# project_2_DDR.net
KiCad netlist of a schematic drawn in EAGLE
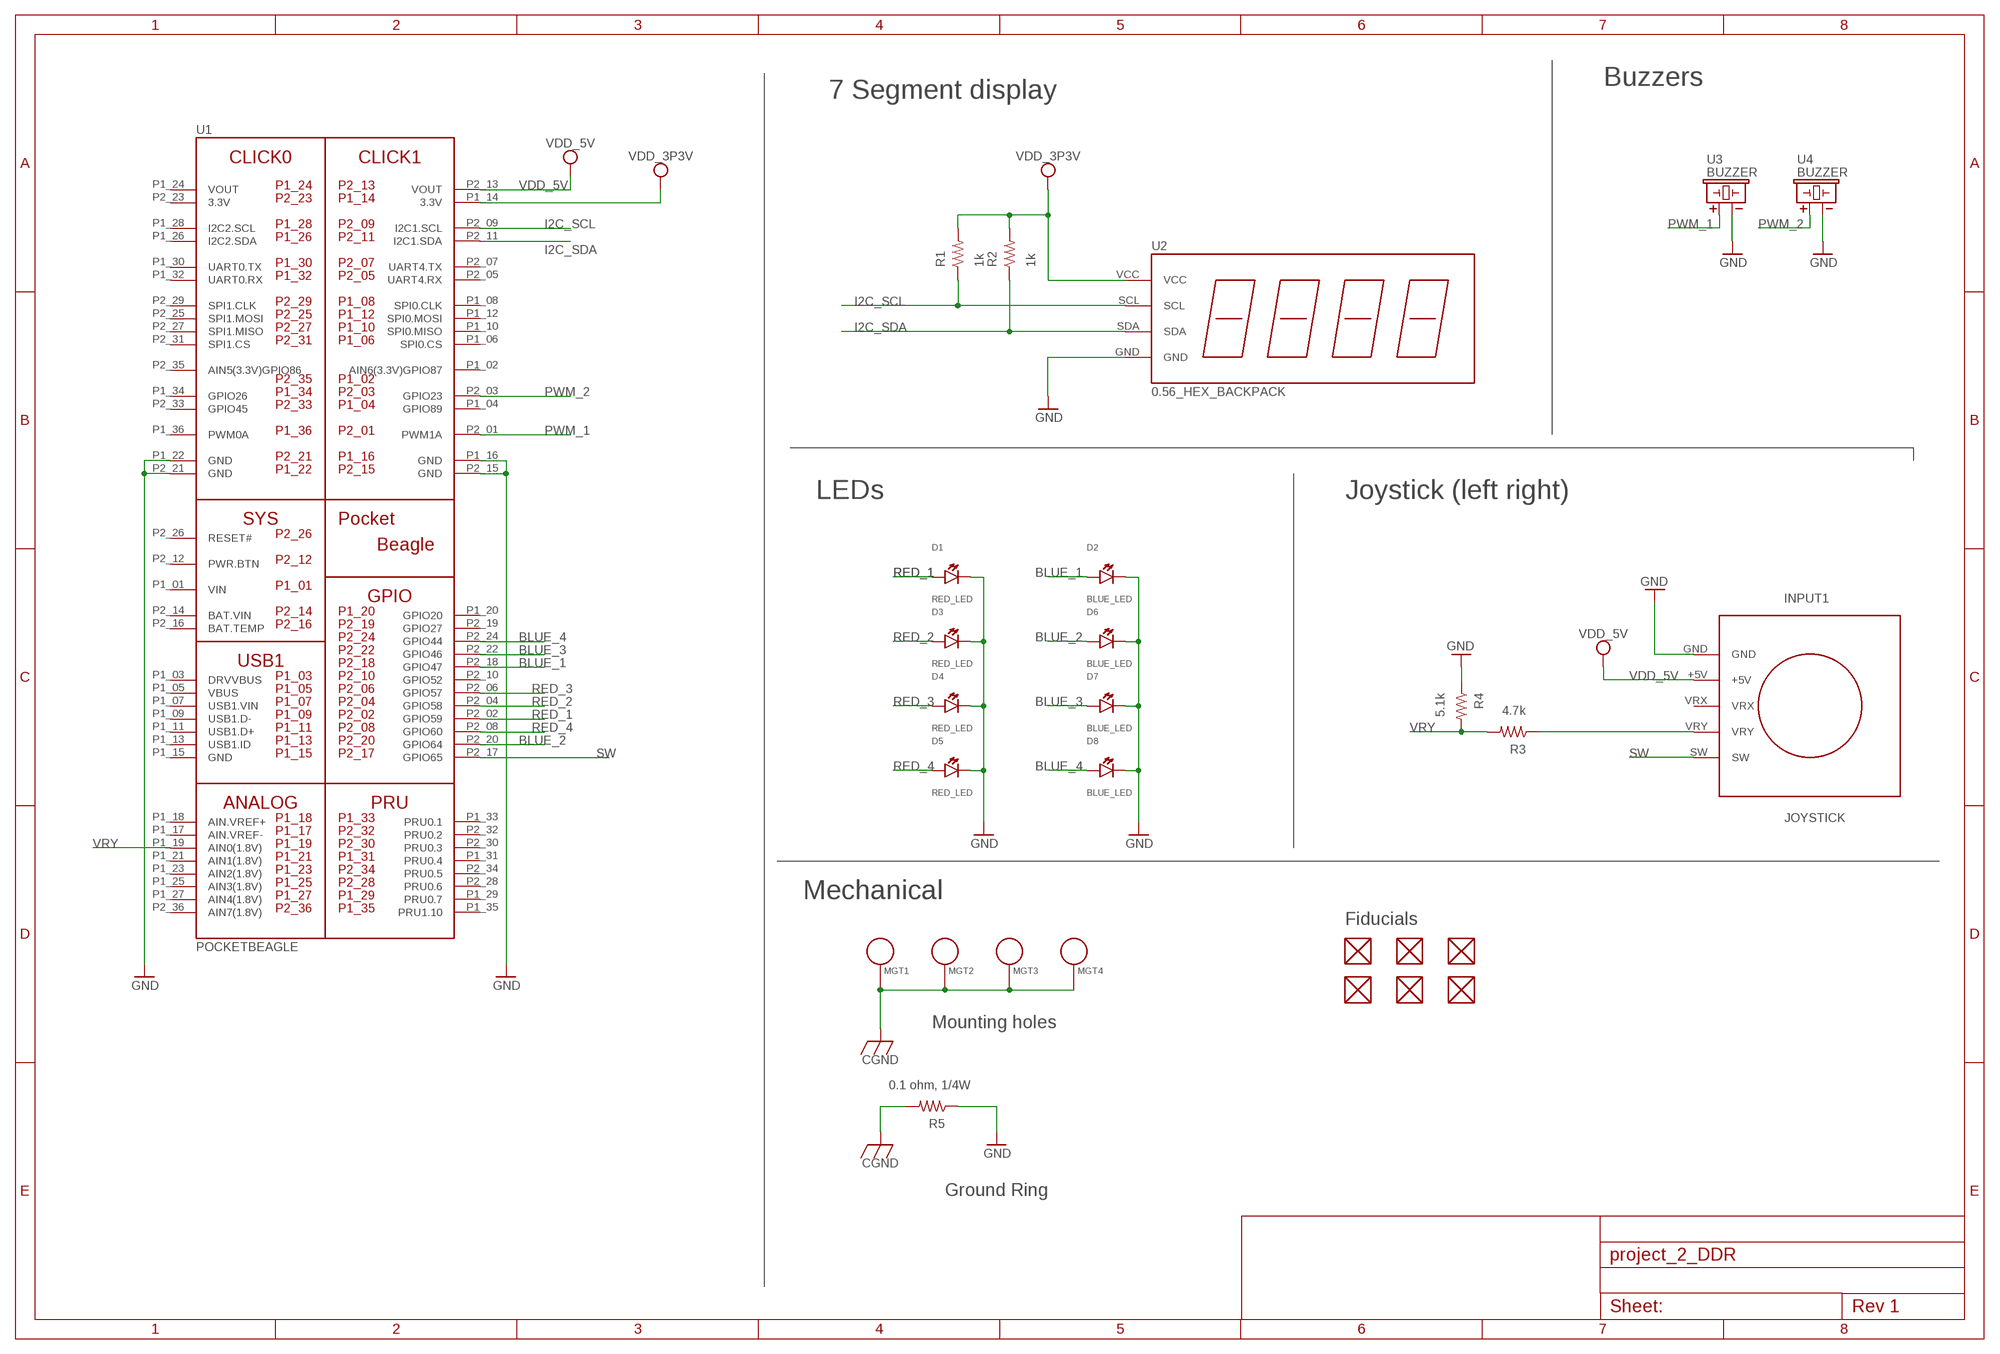
[diagram p0: schematic, sheet 1]

(export (version "E")
  (design (tool "Eeschema 10.0.6"))
  (components
    (comp (ref "D1")
      (value "RED_LED")
      (footprint "eagle-import:EIA-STD")
      (libsource (lib "eagle-import") (part "LED"))
    )
    (comp (ref "D2")
      (value "BLUE_LED")
      (footprint "eagle-import:EIA-STD")
      (libsource (lib "eagle-import") (part "LED"))
    )
    (comp (ref "D3")
      (value "RED_LED")
      (footprint "eagle-import:EIA-STD")
      (libsource (lib "eagle-import") (part "LED"))
    )
    (comp (ref "D4")
      (value "RED_LED")
      (footprint "eagle-import:EIA-STD")
      (libsource (lib "eagle-import") (part "LED"))
    )
    (comp (ref "D5")
      (value "RED_LED")
      (footprint "eagle-import:EIA-STD")
      (libsource (lib "eagle-import") (part "LED"))
    )
    (comp (ref "D6")
      (value "BLUE_LED")
      (footprint "eagle-import:EIA-STD")
      (libsource (lib "eagle-import") (part "LED"))
    )
    (comp (ref "D7")
      (value "BLUE_LED")
      (footprint "eagle-import:EIA-STD")
      (libsource (lib "eagle-import") (part "LED"))
    )
    (comp (ref "D8")
      (value "BLUE_LED")
      (footprint "eagle-import:EIA-STD")
      (libsource (lib "eagle-import") (part "LED"))
    )
    (comp (ref "FUD1")
      (value "FIDUCIAL")
      (footprint "eagle-import:FIDUCIAL_40MIL")
      (libsource (lib "eagle-import") (part "FIDUCIAL"))
    )
    (comp (ref "FUD2")
      (value "FIDUCIAL")
      (footprint "eagle-import:FIDUCIAL_40MIL")
      (libsource (lib "eagle-import") (part "FIDUCIAL"))
    )
    (comp (ref "FUD3")
      (value "FIDUCIAL")
      (footprint "eagle-import:FIDUCIAL_40MIL")
      (libsource (lib "eagle-import") (part "FIDUCIAL"))
    )
    (comp (ref "FUD4")
      (value "FIDUCIAL")
      (footprint "eagle-import:FIDUCIAL_40MIL")
      (libsource (lib "eagle-import") (part "FIDUCIAL"))
    )
    (comp (ref "FUD5")
      (value "FIDUCIAL")
      (footprint "eagle-import:FIDUCIAL_40MIL")
      (libsource (lib "eagle-import") (part "FIDUCIAL"))
    )
    (comp (ref "FUD6")
      (value "FIDUCIAL")
      (footprint "eagle-import:FIDUCIAL_40MIL")
      (libsource (lib "eagle-import") (part "FIDUCIAL"))
    )
    (comp (ref "INPUT1")
      (value "JOYSTICK")
      (footprint "eagle-import:JOYSTICK")
      (libsource (lib "eagle-import") (part "JOYSTICK"))
    )
    (comp (ref "MGT1")
      (value "MOUNTING_HOLE")
      (footprint "eagle-import:MOUNTING_HOLE")
      (libsource (lib "eagle-import") (part "MOUNTING_HOLE"))
    )
    (comp (ref "MGT2")
      (value "MOUNTING_HOLE")
      (footprint "eagle-import:MOUNTING_HOLE")
      (libsource (lib "eagle-import") (part "MOUNTING_HOLE"))
    )
    (comp (ref "MGT3")
      (value "MOUNTING_HOLE")
      (footprint "eagle-import:MOUNTING_HOLE")
      (libsource (lib "eagle-import") (part "MOUNTING_HOLE"))
    )
    (comp (ref "MGT4")
      (value "MOUNTING_HOLE")
      (footprint "eagle-import:MOUNTING_HOLE")
      (libsource (lib "eagle-import") (part "MOUNTING_HOLE"))
    )
    (comp (ref "R1")
      (value "1k")
      (footprint "eagle-import:R0603")
      (libsource (lib "eagle-import") (part "R_R0603"))
    )
    (comp (ref "R2")
      (value "1k")
      (footprint "eagle-import:R0603")
      (libsource (lib "eagle-import") (part "R_R0603"))
    )
    (comp (ref "R3")
      (value "4.7k")
      (footprint "eagle-import:R0603")
      (libsource (lib "eagle-import") (part "R_R0603"))
    )
    (comp (ref "R4")
      (value "5.1k")
      (footprint "eagle-import:R0603")
      (libsource (lib "eagle-import") (part "R_R0603"))
    )
    (comp (ref "R5")
      (value "0.1 ohm, 1/4W")
      (footprint "eagle-import:R0603")
      (libsource (lib "eagle-import") (part "R_R0603"))
    )
    (comp (ref "U1")
      (value "POCKETBEAGLE")
      (footprint "eagle-import:POCKETBEAGLE")
      (libsource (lib "eagle-import") (part "POCKETBEAGLE"))
    )
    (comp (ref "U2")
      (value "0.56_HEX_BACKPACK")
      (footprint "eagle-import:0.56_HEX_BACKPACK")
      (libsource (lib "eagle-import") (part "0.56_HEX_BACKPACK"))
    )
    (comp (ref "U3")
      (value "BUZZER")
      (footprint "eagle-import:BUZZER_6.5MM")
      (libsource (lib "eagle-import") (part "BUZZER"))
    )
    (comp (ref "U4")
      (value "BUZZER")
      (footprint "eagle-import:BUZZER_6.5MM")
      (libsource (lib "eagle-import") (part "BUZZER"))
    )
  )
  (nets
    (net (code "1") (name "/3.3V") (class "Default")
      (node (ref "U1") (pin "P2_23") (pinfunction "3.3V_P2_23") (pintype "power_in"))
    )
    (net (code "2") (name "/BAT.VIN") (class "Default")
      (node (ref "U1") (pin "P2_14") (pinfunction "BAT.VIN_P2_14") (pintype "power_in"))
    )
    (net (code "3") (name "/BLUE_1") (class "Default")
      (node (ref "D2") (pin "ANODE") (pinfunction "ANODE_ANODE") (pintype "bidirectional"))
      (node (ref "U1") (pin "P2_18") (pinfunction "GPIO47_P2_18") (pintype "bidirectional"))
    )
    (net (code "4") (name "/BLUE_2") (class "Default")
      (node (ref "D6") (pin "ANODE") (pinfunction "ANODE_ANODE") (pintype "bidirectional"))
      (node (ref "U1") (pin "P2_20") (pinfunction "GPIO64_P2_20") (pintype "bidirectional"))
    )
    (net (code "5") (name "/BLUE_3") (class "Default")
      (node (ref "D7") (pin "ANODE") (pinfunction "ANODE_ANODE") (pintype "bidirectional"))
      (node (ref "U1") (pin "P2_22") (pinfunction "GPIO46_P2_22") (pintype "bidirectional"))
    )
    (net (code "6") (name "/BLUE_4") (class "Default")
      (node (ref "D8") (pin "ANODE") (pinfunction "ANODE_ANODE") (pintype "bidirectional"))
      (node (ref "U1") (pin "P2_24") (pinfunction "GPIO44_P2_24") (pintype "bidirectional"))
    )
    (net (code "7") (name "/I2C_SCL") (class "Default")
      (node (ref "R1") (pin "1") (pinfunction "1_1") (pintype "passive"))
      (node (ref "U1") (pin "P2_09") (pinfunction "I2C1.SCL_P2_09") (pintype "bidirectional"))
      (node (ref "U2") (pin "SCL") (pinfunction "SCL_SCL") (pintype "bidirectional"))
    )
    (net (code "8") (name "/I2C_SDA") (class "Default")
      (node (ref "R2") (pin "1") (pinfunction "1_1") (pintype "passive"))
      (node (ref "U1") (pin "P2_11") (pinfunction "I2C1.SDA_P2_11") (pintype "bidirectional"))
      (node (ref "U2") (pin "SDA") (pinfunction "SDA_SDA") (pintype "bidirectional"))
    )
    (net (code "9") (name "/PWM_1") (class "Default")
      (node (ref "U1") (pin "P2_01") (pinfunction "PWM1A_P2_01") (pintype "bidirectional"))
      (node (ref "U3") (pin "+") (pinfunction "+_+") (pintype "passive"))
    )
    (net (code "10") (name "/PWM_2") (class "Default")
      (node (ref "U1") (pin "P2_03") (pinfunction "GPIO23_P2_03") (pintype "bidirectional"))
      (node (ref "U4") (pin "+") (pinfunction "+_+") (pintype "passive"))
    )
    (net (code "11") (name "/RED_1") (class "Default")
      (node (ref "D1") (pin "ANODE") (pinfunction "ANODE_ANODE") (pintype "bidirectional"))
      (node (ref "U1") (pin "P2_02") (pinfunction "GPIO59_P2_02") (pintype "bidirectional"))
    )
    (net (code "12") (name "/RED_2") (class "Default")
      (node (ref "D3") (pin "ANODE") (pinfunction "ANODE_ANODE") (pintype "bidirectional"))
      (node (ref "U1") (pin "P2_04") (pinfunction "GPIO58_P2_04") (pintype "bidirectional"))
    )
    (net (code "13") (name "/RED_3") (class "Default")
      (node (ref "D4") (pin "ANODE") (pinfunction "ANODE_ANODE") (pintype "bidirectional"))
      (node (ref "U1") (pin "P2_06") (pinfunction "GPIO57_P2_06") (pintype "bidirectional"))
    )
    (net (code "14") (name "/RED_4") (class "Default")
      (node (ref "D5") (pin "ANODE") (pinfunction "ANODE_ANODE") (pintype "bidirectional"))
      (node (ref "U1") (pin "P2_08") (pinfunction "GPIO60_P2_08") (pintype "bidirectional"))
    )
    (net (code "15") (name "/SW") (class "Default")
      (node (ref "INPUT1") (pin "SW") (pinfunction "SW_SW") (pintype "output"))
      (node (ref "U1") (pin "P2_17") (pinfunction "GPIO65_P2_17") (pintype "bidirectional"))
    )
    (net (code "16") (name "/VIN") (class "Default")
      (node (ref "U1") (pin "P1_01") (pinfunction "VIN_P1_01") (pintype "power_in"))
    )
    (net (code "17") (name "/VOUT") (class "Default")
      (node (ref "U1") (pin "P1_24") (pinfunction "VOUT_P1_24") (pintype "power_in"))
    )
    (net (code "18") (name "/VRY") (class "Default")
      (node (ref "R3") (pin "2") (pinfunction "2_2") (pintype "passive"))
      (node (ref "R4") (pin "2") (pinfunction "2_2") (pintype "passive"))
      (node (ref "U1") (pin "P1_19") (pinfunction "AIN0(1.8V)_P1_19") (pintype "input"))
    )
    (net (code "19") (name "CGND") (class "Default")
      (node (ref "MGT1") (pin "P$1") (pinfunction "P$1_P$1") (pintype "bidirectional"))
      (node (ref "MGT2") (pin "P$1") (pinfunction "P$1_P$1") (pintype "bidirectional"))
      (node (ref "MGT3") (pin "P$1") (pinfunction "P$1_P$1") (pintype "bidirectional"))
      (node (ref "MGT4") (pin "P$1") (pinfunction "P$1_P$1") (pintype "bidirectional"))
      (node (ref "R5") (pin "2") (pinfunction "2_2") (pintype "passive"))
    )
    (net (code "20") (name "GND") (class "Default")
      (node (ref "D1") (pin "CATHODE") (pinfunction "CATHODE_CATHODE") (pintype "bidirectional"))
      (node (ref "D2") (pin "CATHODE") (pinfunction "CATHODE_CATHODE") (pintype "bidirectional"))
      (node (ref "D3") (pin "CATHODE") (pinfunction "CATHODE_CATHODE") (pintype "bidirectional"))
      (node (ref "D4") (pin "CATHODE") (pinfunction "CATHODE_CATHODE") (pintype "bidirectional"))
      (node (ref "D5") (pin "CATHODE") (pinfunction "CATHODE_CATHODE") (pintype "bidirectional"))
      (node (ref "D6") (pin "CATHODE") (pinfunction "CATHODE_CATHODE") (pintype "bidirectional"))
      (node (ref "D7") (pin "CATHODE") (pinfunction "CATHODE_CATHODE") (pintype "bidirectional"))
      (node (ref "D8") (pin "CATHODE") (pinfunction "CATHODE_CATHODE") (pintype "bidirectional"))
      (node (ref "INPUT1") (pin "GND") (pinfunction "GND_GND") (pintype "bidirectional"))
      (node (ref "R4") (pin "1") (pinfunction "1_1") (pintype "passive"))
      (node (ref "R5") (pin "1") (pinfunction "1_1") (pintype "passive"))
      (node (ref "U1") (pin "P1_16") (pinfunction "GND_P1_16") (pintype "power_in"))
      (node (ref "U1") (pin "P1_22") (pinfunction "GND_P1_22") (pintype "power_in"))
      (node (ref "U1") (pin "P2_15") (pinfunction "GND_P2_15") (pintype "power_in"))
      (node (ref "U1") (pin "P2_21") (pinfunction "GND_P2_21") (pintype "power_in"))
      (node (ref "U2") (pin "GND") (pinfunction "GND_GND") (pintype "bidirectional"))
      (node (ref "U3") (pin "-") (pinfunction "-_-") (pintype "passive"))
      (node (ref "U4") (pin "-") (pinfunction "-_-") (pintype "passive"))
    )
    (net (code "21") (name "Net-(INPUT1-PadVRY)") (class "Default")
      (node (ref "INPUT1") (pin "VRY") (pinfunction "VRY_VRY") (pintype "output"))
      (node (ref "R3") (pin "1") (pinfunction "1_1") (pintype "passive"))
    )
    (net (code "22") (name "VDD_3P3V") (class "Default")
      (node (ref "R1") (pin "2") (pinfunction "2_2") (pintype "passive"))
      (node (ref "R2") (pin "2") (pinfunction "2_2") (pintype "passive"))
      (node (ref "U1") (pin "P1_14") (pinfunction "3.3V_P1_14") (pintype "power_in"))
      (node (ref "U2") (pin "VCC") (pinfunction "VCC_VCC") (pintype "power_in"))
    )
    (net (code "23") (name "VDD_5V") (class "Default")
      (node (ref "INPUT1") (pin "+5V") (pinfunction "+5V_+5V") (pintype "power_in"))
      (node (ref "U1") (pin "P2_13") (pinfunction "VOUT_P2_13") (pintype "power_in"))
    )
    (net (code "24") (name "unconnected-(FUD1-PadP$1)") (class "Default")
      (node (ref "FUD1") (pin "P$1") (pinfunction "P$1_P$1") (pintype "no_connect"))
    )
    (net (code "25") (name "unconnected-(FUD2-PadP$1)") (class "Default")
      (node (ref "FUD2") (pin "P$1") (pinfunction "P$1_P$1") (pintype "no_connect"))
    )
    (net (code "26") (name "unconnected-(FUD3-PadP$1)") (class "Default")
      (node (ref "FUD3") (pin "P$1") (pinfunction "P$1_P$1") (pintype "no_connect"))
    )
    (net (code "27") (name "unconnected-(FUD4-PadP$1)") (class "Default")
      (node (ref "FUD4") (pin "P$1") (pinfunction "P$1_P$1") (pintype "no_connect"))
    )
    (net (code "28") (name "unconnected-(FUD5-PadP$1)") (class "Default")
      (node (ref "FUD5") (pin "P$1") (pinfunction "P$1_P$1") (pintype "no_connect"))
    )
    (net (code "29") (name "unconnected-(FUD6-PadP$1)") (class "Default")
      (node (ref "FUD6") (pin "P$1") (pinfunction "P$1_P$1") (pintype "no_connect"))
    )
    (net (code "30") (name "unconnected-(INPUT1-PadVRX)") (class "Default")
      (node (ref "INPUT1") (pin "VRX") (pinfunction "VRX_VRX") (pintype "output"))
    )
    (net (code "31") (name "unconnected-(U1-AIN.VREF+-PadP1_18)") (class "Default")
      (node (ref "U1") (pin "P1_18") (pinfunction "AIN.VREF+_P1_18") (pintype "input"))
    )
    (net (code "32") (name "unconnected-(U1-AIN.VREF--PadP1_17)") (class "Default")
      (node (ref "U1") (pin "P1_17") (pinfunction "AIN.VREF-_P1_17") (pintype "input"))
    )
    (net (code "33") (name "unconnected-(U1-AIN1(1.8V)-PadP1_21)") (class "Default")
      (node (ref "U1") (pin "P1_21") (pinfunction "AIN1(1.8V)_P1_21") (pintype "input"))
    )
    (net (code "34") (name "unconnected-(U1-AIN2(1.8V)-PadP1_23)") (class "Default")
      (node (ref "U1") (pin "P1_23") (pinfunction "AIN2(1.8V)_P1_23") (pintype "input"))
    )
    (net (code "35") (name "unconnected-(U1-AIN3(1.8V)-PadP1_25)") (class "Default")
      (node (ref "U1") (pin "P1_25") (pinfunction "AIN3(1.8V)_P1_25") (pintype "input"))
    )
    (net (code "36") (name "unconnected-(U1-AIN4(1.8V)-PadP1_27)") (class "Default")
      (node (ref "U1") (pin "P1_27") (pinfunction "AIN4(1.8V)_P1_27") (pintype "input"))
    )
    (net (code "37") (name "unconnected-(U1-AIN5(3.3V)GPIO86-PadP2_35)") (class "Default")
      (node (ref "U1") (pin "P2_35") (pinfunction "AIN5(3.3V)GPIO86_P2_35") (pintype "bidirectional"))
    )
    (net (code "38") (name "unconnected-(U1-AIN6(3.3V)GPIO87-PadP1_02)") (class "Default")
      (node (ref "U1") (pin "P1_02") (pinfunction "AIN6(3.3V)GPIO87_P1_02") (pintype "bidirectional"))
    )
    (net (code "39") (name "unconnected-(U1-AIN7(1.8V)-PadP2_36)") (class "Default")
      (node (ref "U1") (pin "P2_36") (pinfunction "AIN7(1.8V)_P2_36") (pintype "input"))
    )
    (net (code "40") (name "unconnected-(U1-BAT.TEMP-PadP2_16)") (class "Default")
      (node (ref "U1") (pin "P2_16") (pinfunction "BAT.TEMP_P2_16") (pintype "input"))
    )
    (net (code "41") (name "unconnected-(U1-DRVVBUS-PadP1_03)") (class "Default")
      (node (ref "U1") (pin "P1_03") (pinfunction "DRVVBUS_P1_03") (pintype "bidirectional"))
    )
    (net (code "42") (name "unconnected-(U1-GND-PadP1_15)") (class "Default")
      (node (ref "U1") (pin "P1_15") (pinfunction "GND_P1_15") (pintype "bidirectional"))
    )
    (net (code "43") (name "unconnected-(U1-GPIO20-PadP1_20)") (class "Default")
      (node (ref "U1") (pin "P1_20") (pinfunction "GPIO20_P1_20") (pintype "bidirectional"))
    )
    (net (code "44") (name "unconnected-(U1-GPIO26-PadP1_34)") (class "Default")
      (node (ref "U1") (pin "P1_34") (pinfunction "GPIO26_P1_34") (pintype "bidirectional"))
    )
    (net (code "45") (name "unconnected-(U1-GPIO27-PadP2_19)") (class "Default")
      (node (ref "U1") (pin "P2_19") (pinfunction "GPIO27_P2_19") (pintype "bidirectional"))
    )
    (net (code "46") (name "unconnected-(U1-GPIO45-PadP2_33)") (class "Default")
      (node (ref "U1") (pin "P2_33") (pinfunction "GPIO45_P2_33") (pintype "bidirectional"))
    )
    (net (code "47") (name "unconnected-(U1-GPIO52-PadP2_10)") (class "Default")
      (node (ref "U1") (pin "P2_10") (pinfunction "GPIO52_P2_10") (pintype "bidirectional"))
    )
    (net (code "48") (name "unconnected-(U1-GPIO89-PadP1_04)") (class "Default")
      (node (ref "U1") (pin "P1_04") (pinfunction "GPIO89_P1_04") (pintype "bidirectional"))
    )
    (net (code "49") (name "unconnected-(U1-I2C2.SCL-PadP1_28)") (class "Default")
      (node (ref "U1") (pin "P1_28") (pinfunction "I2C2.SCL_P1_28") (pintype "bidirectional"))
    )
    (net (code "50") (name "unconnected-(U1-I2C2.SDA-PadP1_26)") (class "Default")
      (node (ref "U1") (pin "P1_26") (pinfunction "I2C2.SDA_P1_26") (pintype "bidirectional"))
    )
    (net (code "51") (name "unconnected-(U1-PRU0.1-PadP1_33)") (class "Default")
      (node (ref "U1") (pin "P1_33") (pinfunction "PRU0.1_P1_33") (pintype "bidirectional"))
    )
    (net (code "52") (name "unconnected-(U1-PRU0.2-PadP2_32)") (class "Default")
      (node (ref "U1") (pin "P2_32") (pinfunction "PRU0.2_P2_32") (pintype "bidirectional"))
    )
    (net (code "53") (name "unconnected-(U1-PRU0.3-PadP2_30)") (class "Default")
      (node (ref "U1") (pin "P2_30") (pinfunction "PRU0.3_P2_30") (pintype "bidirectional"))
    )
    (net (code "54") (name "unconnected-(U1-PRU0.4-PadP1_31)") (class "Default")
      (node (ref "U1") (pin "P1_31") (pinfunction "PRU0.4_P1_31") (pintype "bidirectional"))
    )
    (net (code "55") (name "unconnected-(U1-PRU0.5-PadP2_34)") (class "Default")
      (node (ref "U1") (pin "P2_34") (pinfunction "PRU0.5_P2_34") (pintype "bidirectional"))
    )
    (net (code "56") (name "unconnected-(U1-PRU0.6-PadP2_28)") (class "Default")
      (node (ref "U1") (pin "P2_28") (pinfunction "PRU0.6_P2_28") (pintype "bidirectional"))
    )
    (net (code "57") (name "unconnected-(U1-PRU0.7-PadP1_29)") (class "Default")
      (node (ref "U1") (pin "P1_29") (pinfunction "PRU0.7_P1_29") (pintype "bidirectional"))
    )
    (net (code "58") (name "unconnected-(U1-PRU1.10-PadP1_35)") (class "Default")
      (node (ref "U1") (pin "P1_35") (pinfunction "PRU1.10_P1_35") (pintype "bidirectional"))
    )
    (net (code "59") (name "unconnected-(U1-PWM0A-PadP1_36)") (class "Default")
      (node (ref "U1") (pin "P1_36") (pinfunction "PWM0A_P1_36") (pintype "bidirectional"))
    )
    (net (code "60") (name "unconnected-(U1-PWR.BTN-PadP2_12)") (class "Default")
      (node (ref "U1") (pin "P2_12") (pinfunction "PWR.BTN_P2_12") (pintype "input"))
    )
    (net (code "61") (name "unconnected-(U1-RESET#-PadP2_26)") (class "Default")
      (node (ref "U1") (pin "P2_26") (pinfunction "RESET#_P2_26") (pintype "input"))
    )
    (net (code "62") (name "unconnected-(U1-SPI0.CLK-PadP1_08)") (class "Default")
      (node (ref "U1") (pin "P1_08") (pinfunction "SPI0.CLK_P1_08") (pintype "bidirectional"))
    )
    (net (code "63") (name "unconnected-(U1-SPI0.CS-PadP1_06)") (class "Default")
      (node (ref "U1") (pin "P1_06") (pinfunction "SPI0.CS_P1_06") (pintype "bidirectional"))
    )
    (net (code "64") (name "unconnected-(U1-SPI0.MISO-PadP1_10)") (class "Default")
      (node (ref "U1") (pin "P1_10") (pinfunction "SPI0.MISO_P1_10") (pintype "bidirectional"))
    )
    (net (code "65") (name "unconnected-(U1-SPI0.MOSI-PadP1_12)") (class "Default")
      (node (ref "U1") (pin "P1_12") (pinfunction "SPI0.MOSI_P1_12") (pintype "bidirectional"))
    )
    (net (code "66") (name "unconnected-(U1-SPI1.CLK-PadP2_29)") (class "Default")
      (node (ref "U1") (pin "P2_29") (pinfunction "SPI1.CLK_P2_29") (pintype "bidirectional"))
    )
    (net (code "67") (name "unconnected-(U1-SPI1.CS-PadP2_31)") (class "Default")
      (node (ref "U1") (pin "P2_31") (pinfunction "SPI1.CS_P2_31") (pintype "bidirectional"))
    )
    (net (code "68") (name "unconnected-(U1-SPI1.MISO-PadP2_27)") (class "Default")
      (node (ref "U1") (pin "P2_27") (pinfunction "SPI1.MISO_P2_27") (pintype "bidirectional"))
    )
    (net (code "69") (name "unconnected-(U1-SPI1.MOSI-PadP2_25)") (class "Default")
      (node (ref "U1") (pin "P2_25") (pinfunction "SPI1.MOSI_P2_25") (pintype "bidirectional"))
    )
    (net (code "70") (name "unconnected-(U1-UART0.RX-PadP1_32)") (class "Default")
      (node (ref "U1") (pin "P1_32") (pinfunction "UART0.RX_P1_32") (pintype "bidirectional"))
    )
    (net (code "71") (name "unconnected-(U1-UART0.TX-PadP1_30)") (class "Default")
      (node (ref "U1") (pin "P1_30") (pinfunction "UART0.TX_P1_30") (pintype "bidirectional"))
    )
    (net (code "72") (name "unconnected-(U1-UART4.RX-PadP2_05)") (class "Default")
      (node (ref "U1") (pin "P2_05") (pinfunction "UART4.RX_P2_05") (pintype "bidirectional"))
    )
    (net (code "73") (name "unconnected-(U1-UART4.TX-PadP2_07)") (class "Default")
      (node (ref "U1") (pin "P2_07") (pinfunction "UART4.TX_P2_07") (pintype "bidirectional"))
    )
    (net (code "74") (name "unconnected-(U1-USB1.D+-PadP1_11)") (class "Default")
      (node (ref "U1") (pin "P1_11") (pinfunction "USB1.D+_P1_11") (pintype "bidirectional"))
    )
    (net (code "75") (name "unconnected-(U1-USB1.D--PadP1_09)") (class "Default")
      (node (ref "U1") (pin "P1_09") (pinfunction "USB1.D-_P1_09") (pintype "bidirectional"))
    )
    (net (code "76") (name "unconnected-(U1-USB1.ID-PadP1_13)") (class "Default")
      (node (ref "U1") (pin "P1_13") (pinfunction "USB1.ID_P1_13") (pintype "bidirectional"))
    )
    (net (code "77") (name "unconnected-(U1-USB1.VIN-PadP1_07)") (class "Default")
      (node (ref "U1") (pin "P1_07") (pinfunction "USB1.VIN_P1_07") (pintype "bidirectional"))
    )
    (net (code "78") (name "unconnected-(U1-VBUS-PadP1_05)") (class "Default")
      (node (ref "U1") (pin "P1_05") (pinfunction "VBUS_P1_05") (pintype "bidirectional"))
    )
  )
)
